# ub-1.net
KiCad netlist of a schematic drawn in EAGLE
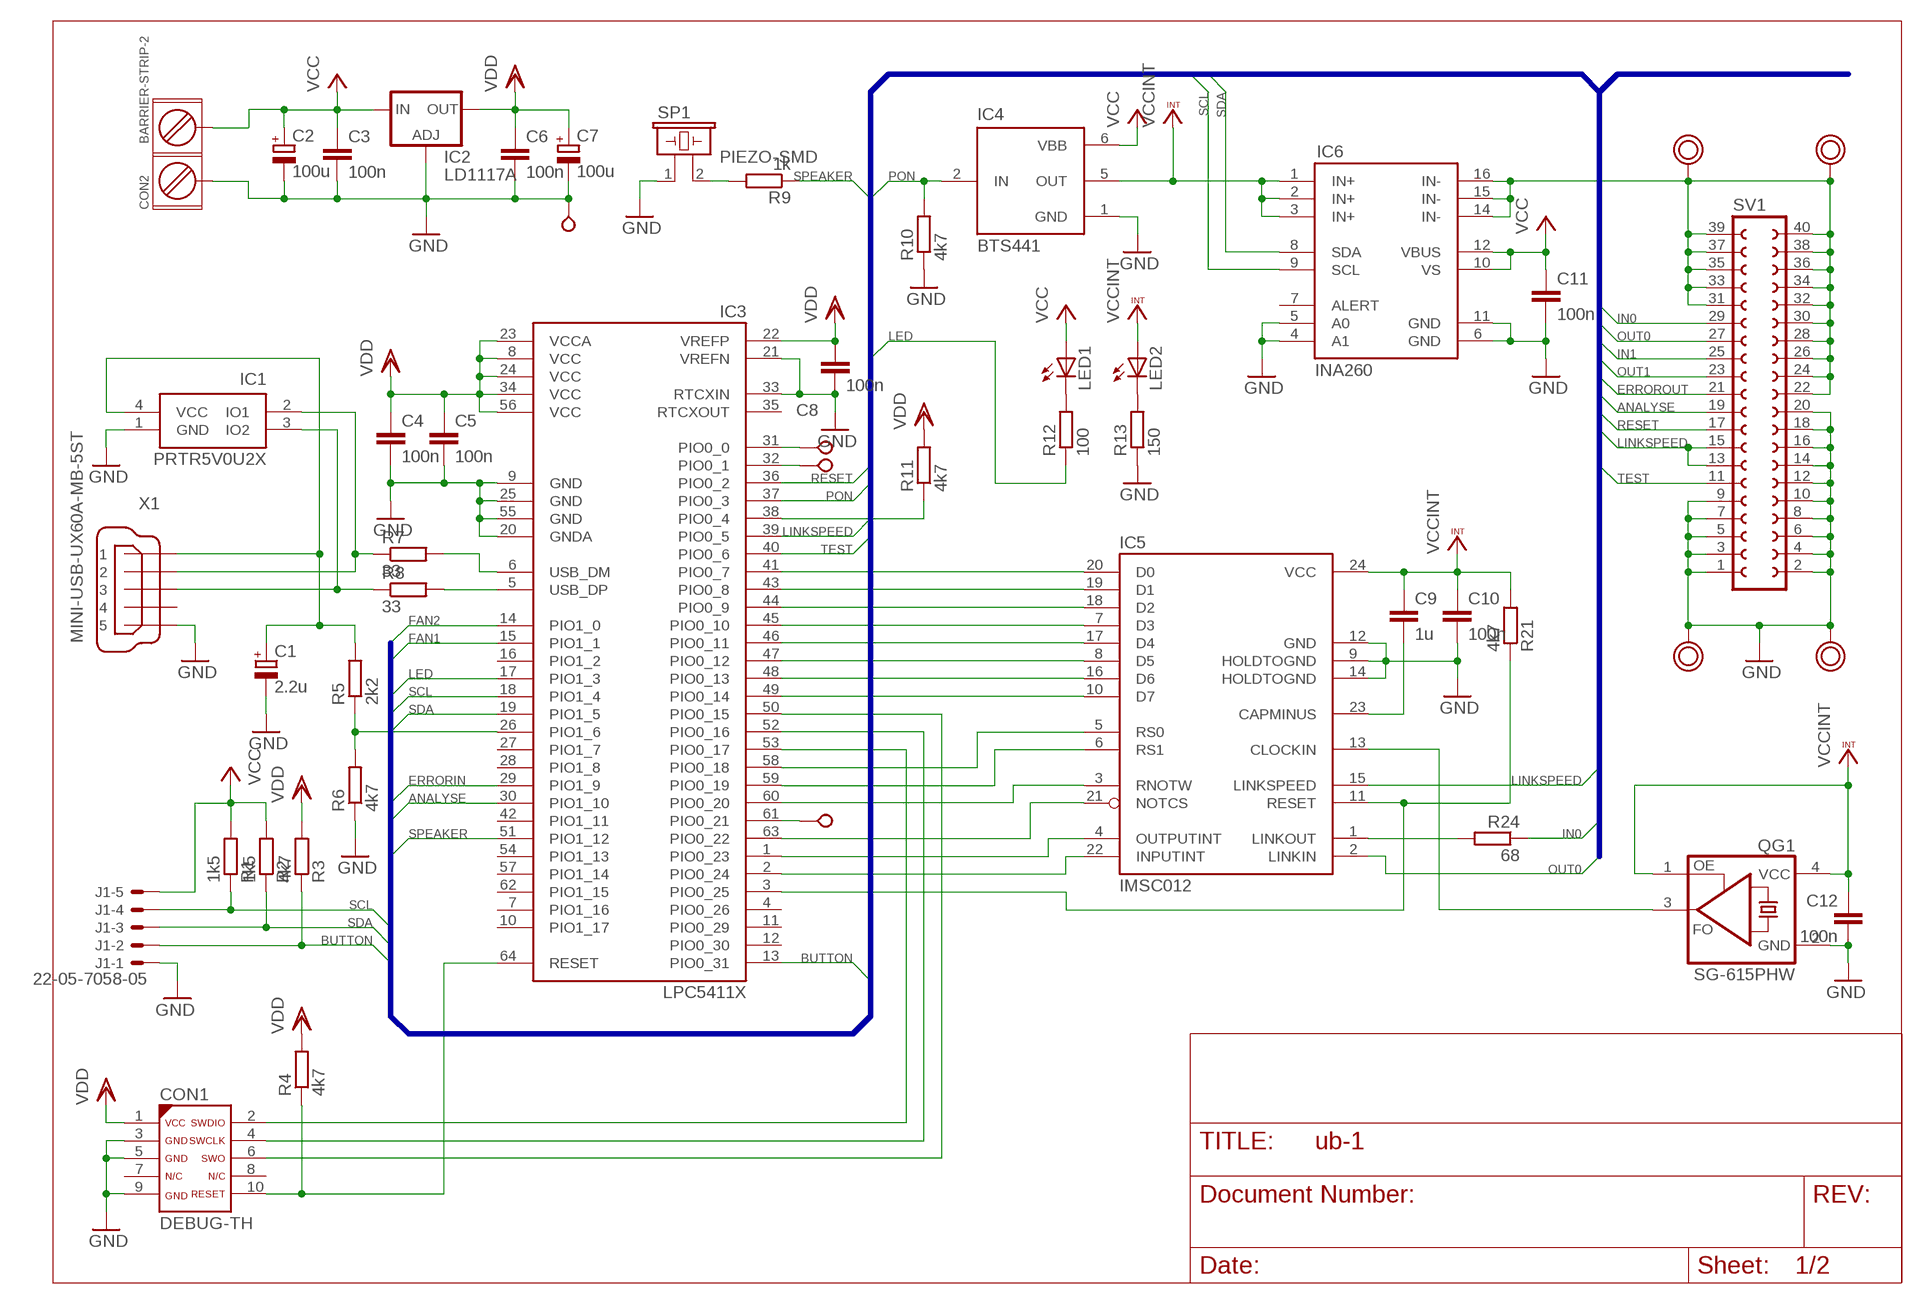
[diagram p0: schematic, sheet 1]
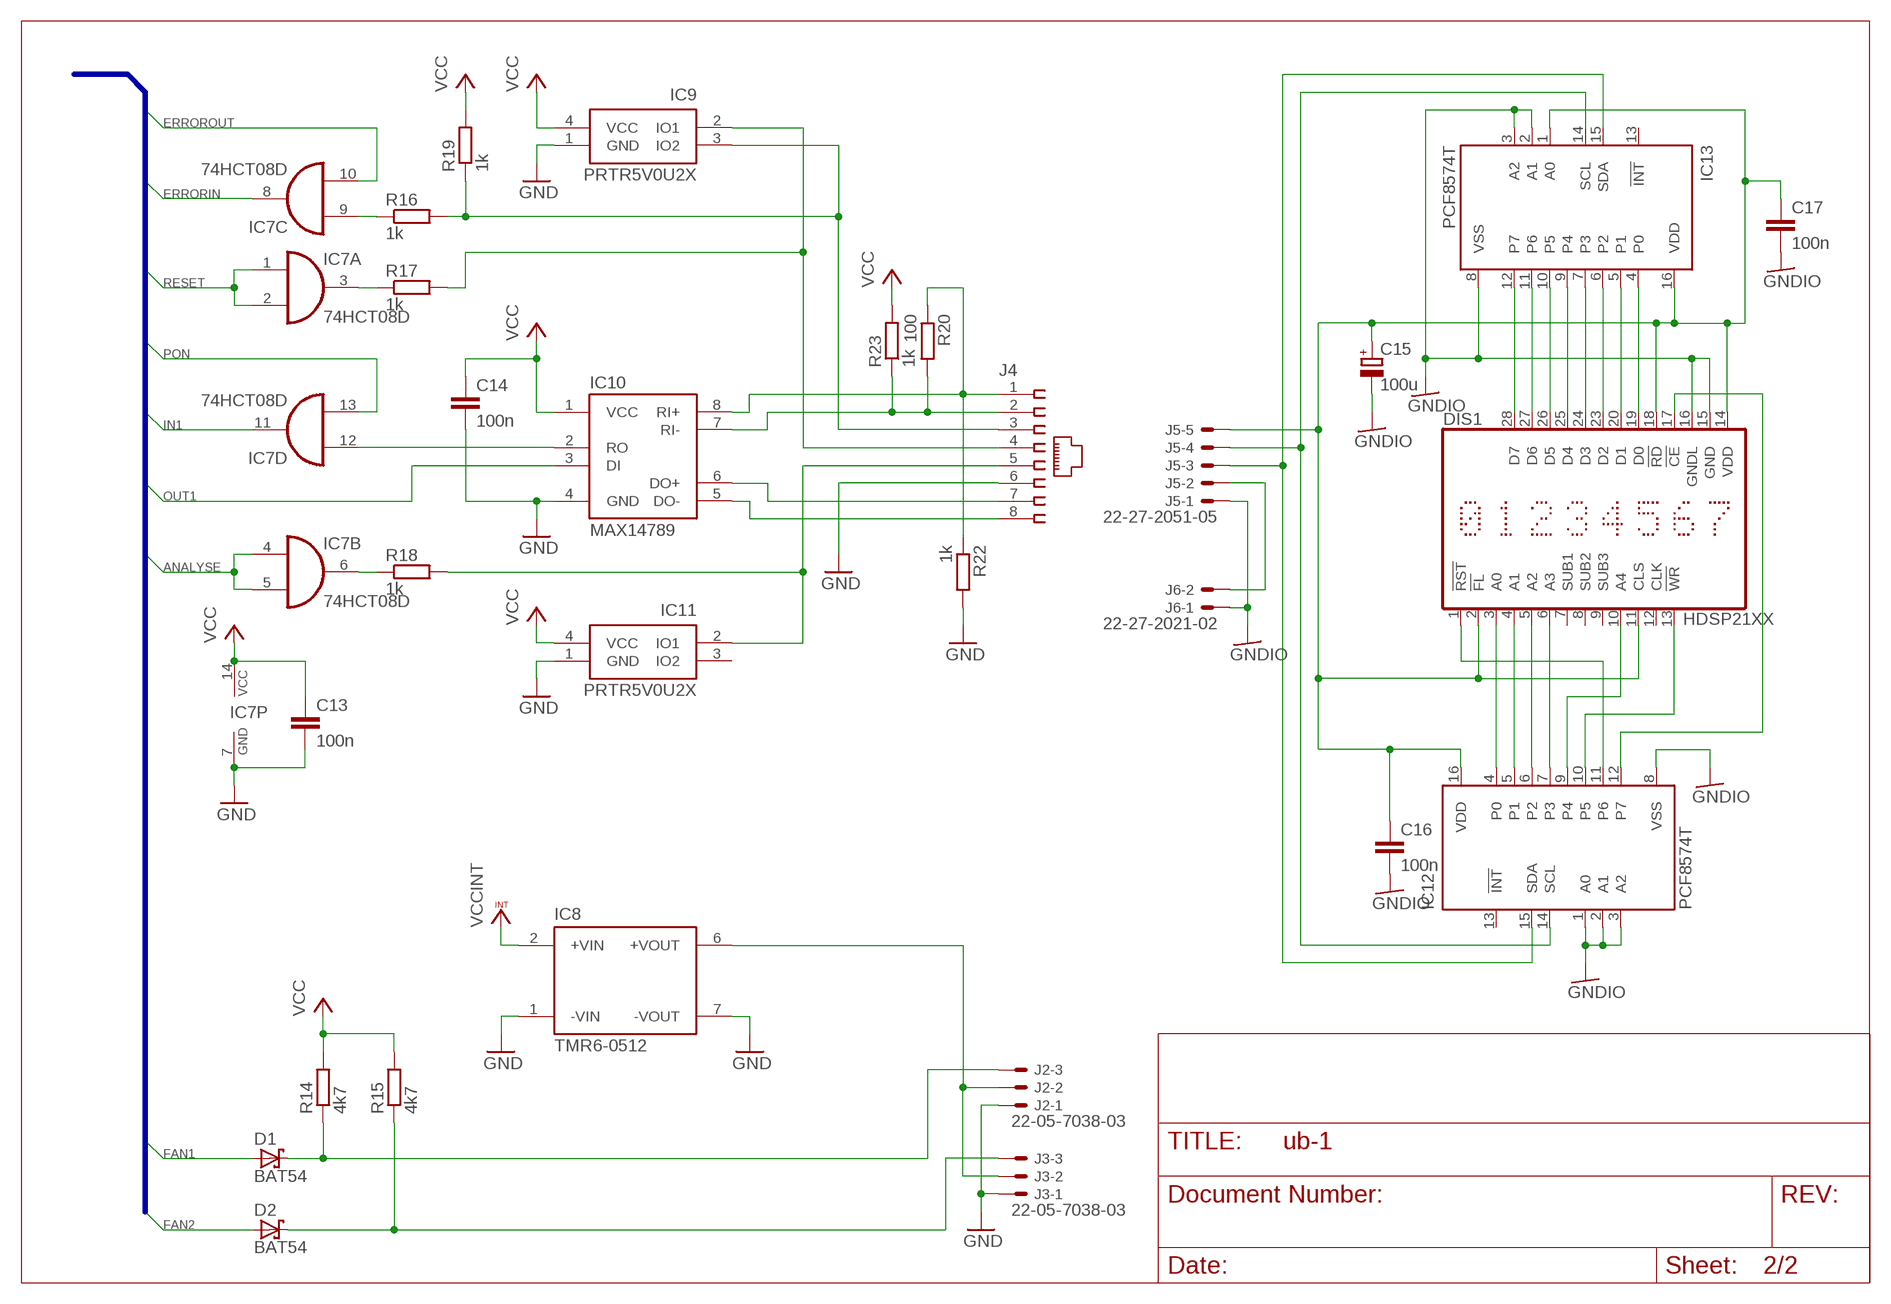
[diagram p1: schematic, sheet 2]

(export (version "E")
  (design (tool "Eeschema 10.0.6"))
  (components
    (comp (ref "C13")
      (value "100n")
      (footprint "eagle-import:C1206")
      (libsource (lib "eagle-import") (part "C-EUC1206"))
    )
    (comp (ref "C14")
      (value "100n")
      (footprint "eagle-import:C1206")
      (libsource (lib "eagle-import") (part "C-EUC1206"))
    )
    (comp (ref "C15")
      (value "100u")
      (footprint "eagle-import:SMC_B")
      (libsource (lib "eagle-import") (part "CPOL-EUSMCB"))
    )
    (comp (ref "C16")
      (value "100n")
      (footprint "eagle-import:C1206")
      (libsource (lib "eagle-import") (part "C-EUC1206"))
    )
    (comp (ref "C17")
      (value "100n")
      (footprint "eagle-import:C1206")
      (libsource (lib "eagle-import") (part "C-EUC1206"))
    )
    (comp (ref "D1")
      (value "BAT54")
      (footprint "eagle-import:SOT23")
      (libsource (lib "eagle-import") (part "BAT54"))
    )
    (comp (ref "D2")
      (value "BAT54")
      (footprint "eagle-import:SOT23")
      (libsource (lib "eagle-import") (part "BAT54"))
    )
    (comp (ref "DIS1")
      (value "HDSP21XX")
      (footprint "eagle-import:HDSP21XX")
      (fields (field (name "MF") "AGILENT TECHNOLOGIES") (field (name "MPN") "HDSP-2179"))
      (libsource (lib "eagle-import") (part "HDSP21XX"))
    )
    (comp (ref "IC7")
      (value "74HCT08D")
      (footprint "eagle-import:SO14")
      (fields (field (name "DIGIKEY") "296-14862-1-ND"))
      (libsource (lib "eagle-import") (part "7408DHCT"))
    )
    (comp (ref "IC8")
      (value "TMR6-0512")
      (footprint "eagle-import:TMR6-0512")
      (libsource (lib "eagle-import") (part "TMR6-0512"))
    )
    (comp (ref "IC9")
      (value "PRTR5V0U2X")
      (footprint "eagle-import:SOT143")
      (libsource (lib "eagle-import") (part "PRTR5V0U2X"))
    )
    (comp (ref "IC10")
      (value "MAX14789")
      (footprint "eagle-import:SO8")
      (libsource (lib "eagle-import") (part "DS8921"))
    )
    (comp (ref "IC11")
      (value "PRTR5V0U2X")
      (footprint "eagle-import:SOT143")
      (libsource (lib "eagle-import") (part "PRTR5V0U2X"))
    )
    (comp (ref "IC12")
      (value "PCF8574T")
      (footprint "eagle-import:SO16W")
      (fields (field (name "MPN") "PCF8574T/3,512"))
      (libsource (lib "eagle-import") (part "PCF8574T"))
    )
    (comp (ref "IC13")
      (value "PCF8574T")
      (footprint "eagle-import:SO16W")
      (fields (field (name "MPN") "PCF8574T/3,512"))
      (libsource (lib "eagle-import") (part "PCF8574T"))
    )
    (comp (ref "J2")
      (value "22-05-7038-03")
      (footprint "eagle-import:7395-03")
      (fields (field (name "DIGIKEY") "WM2785-ND"))
      (libsource (lib "eagle-import") (part "22-?-0305-7038"))
    )
    (comp (ref "J3")
      (value "22-05-7038-03")
      (footprint "eagle-import:7395-03")
      (fields (field (name "DIGIKEY") "WM2785-ND"))
      (libsource (lib "eagle-import") (part "22-?-0305-7038"))
    )
    (comp (ref "J4")
      (value "555164-1")
      (footprint "eagle-import:555164-1")
      (libsource (lib "eagle-import") (part "555164-1"))
    )
    (comp (ref "J5")
      (value "22-27-2051-05")
      (footprint "eagle-import:6410-05")
      (fields (field (name "DIGIKEY") "WM4114-ND"))
      (libsource (lib "eagle-import") (part "22-?-0527-2051"))
    )
    (comp (ref "J6")
      (value "22-27-2021-02")
      (footprint "eagle-import:6410-02")
      (fields (field (name "DIGIKEY") "WM4111-ND"))
      (libsource (lib "eagle-import") (part "22-?-0227-2021"))
    )
    (comp (ref "R14")
      (value "4k7")
      (footprint "eagle-import:R1206")
      (libsource (lib "eagle-import") (part "R-EU_R1206"))
    )
    (comp (ref "R15")
      (value "4k7")
      (footprint "eagle-import:R1206")
      (libsource (lib "eagle-import") (part "R-EU_R1206"))
    )
    (comp (ref "R16")
      (value "1k")
      (footprint "eagle-import:R1206")
      (libsource (lib "eagle-import") (part "R-EU_R1206"))
    )
    (comp (ref "R17")
      (value "1k")
      (footprint "eagle-import:R1206")
      (libsource (lib "eagle-import") (part "R-EU_R1206"))
    )
    (comp (ref "R18")
      (value "1k")
      (footprint "eagle-import:R1206")
      (libsource (lib "eagle-import") (part "R-EU_R1206"))
    )
    (comp (ref "R19")
      (value "1k")
      (footprint "eagle-import:R1206")
      (libsource (lib "eagle-import") (part "R-EU_R1206"))
    )
    (comp (ref "R20")
      (value "100")
      (footprint "eagle-import:R1206")
      (libsource (lib "eagle-import") (part "R-EU_R1206"))
    )
    (comp (ref "R22")
      (value "1k")
      (footprint "eagle-import:R1206")
      (libsource (lib "eagle-import") (part "R-EU_R1206"))
    )
    (comp (ref "R23")
      (value "1k")
      (footprint "eagle-import:R1206")
      (libsource (lib "eagle-import") (part "R-EU_R1206"))
    )
    (comp (ref "C1")
      (value "2.2u")
      (footprint "eagle-import:SMC_B")
      (libsource (lib "eagle-import") (part "CPOL-EUSMCB"))
    )
    (comp (ref "C2")
      (value "100u")
      (footprint "eagle-import:SMC_B")
      (libsource (lib "eagle-import") (part "CPOL-EUSMCB"))
    )
    (comp (ref "C3")
      (value "100n")
      (footprint "eagle-import:C1206")
      (libsource (lib "eagle-import") (part "C-EUC1206"))
    )
    (comp (ref "C4")
      (value "100n")
      (footprint "eagle-import:C1206")
      (libsource (lib "eagle-import") (part "C-EUC1206"))
    )
    (comp (ref "C5")
      (value "100n")
      (footprint "eagle-import:C1206")
      (libsource (lib "eagle-import") (part "C-EUC1206"))
    )
    (comp (ref "C6")
      (value "100n")
      (footprint "eagle-import:C1206")
      (libsource (lib "eagle-import") (part "C-EUC1206"))
    )
    (comp (ref "C7")
      (value "100u")
      (footprint "eagle-import:SMC_B")
      (libsource (lib "eagle-import") (part "CPOL-EUSMCB"))
    )
    (comp (ref "C8")
      (value "100n")
      (footprint "eagle-import:C1206")
      (libsource (lib "eagle-import") (part "C-EUC1206"))
    )
    (comp (ref "C9")
      (value "1u")
      (footprint "eagle-import:C1206")
      (libsource (lib "eagle-import") (part "C-EUC1206"))
    )
    (comp (ref "C10")
      (value "100n")
      (footprint "eagle-import:C1206")
      (libsource (lib "eagle-import") (part "C-EUC1206"))
    )
    (comp (ref "C11")
      (value "100n")
      (footprint "eagle-import:C1206")
      (libsource (lib "eagle-import") (part "C-EUC1206"))
    )
    (comp (ref "C12")
      (value "100n")
      (footprint "eagle-import:C1206")
      (libsource (lib "eagle-import") (part "C-EUC1206"))
    )
    (comp (ref "CON1")
      (value "DEBUG-TH")
      (footprint "eagle-import:DEBUG-TH")
      (libsource (lib "eagle-import") (part "DEBUG-TH"))
    )
    (comp (ref "CON2")
      (value "BARRIER-STRIP-2")
      (footprint "eagle-import:BARRIER-STRIP-2")
      (libsource (lib "eagle-import") (part "BARRIER-STRIP-2"))
    )
    (comp (ref "IC1")
      (value "PRTR5V0U2X")
      (footprint "eagle-import:SOT143")
      (libsource (lib "eagle-import") (part "PRTR5V0U2X"))
    )
    (comp (ref "IC2")
      (value "LD1117A")
      (footprint "eagle-import:SOT223")
      (libsource (lib "eagle-import") (part "LD1117A"))
    )
    (comp (ref "IC3")
      (value "LPC5411X")
      (footprint "eagle-import:LQPF64")
      (libsource (lib "eagle-import") (part "LPC5411X"))
    )
    (comp (ref "IC4")
      (value "BTS441")
      (footprint "eagle-import:TO263-4")
      (libsource (lib "eagle-import") (part "BTS441"))
    )
    (comp (ref "IC5")
      (value "IMSC012")
      (footprint "eagle-import:DIL24-3")
      (libsource (lib "eagle-import") (part "IMSC012"))
    )
    (comp (ref "IC6")
      (value "INA260")
      (footprint "eagle-import:TSSOP-16")
      (libsource (lib "eagle-import") (part "INA260"))
    )
    (comp (ref "J1")
      (value "22-05-7058-05")
      (footprint "eagle-import:7395-05")
      (fields (field (name "DIGIKEY") "WM2787-ND"))
      (libsource (lib "eagle-import") (part "22-?-0505-7058"))
    )
    (comp (ref "LED1")
      (value "LEDSMT1206")
      (footprint "eagle-import:1206")
      (libsource (lib "eagle-import") (part "LEDSMT1206"))
    )
    (comp (ref "LED2")
      (value "LEDSMT1206")
      (footprint "eagle-import:1206")
      (libsource (lib "eagle-import") (part "LEDSMT1206"))
    )
    (comp (ref "QG1")
      (value "SG-615PHW")
      (footprint "eagle-import:SG-615")
      (libsource (lib "eagle-import") (part "SG-615PHW"))
    )
    (comp (ref "R1")
      (value "1k5")
      (footprint "eagle-import:R1206")
      (libsource (lib "eagle-import") (part "R-EU_R1206"))
    )
    (comp (ref "R2")
      (value "1k5")
      (footprint "eagle-import:R1206")
      (libsource (lib "eagle-import") (part "R-EU_R1206"))
    )
    (comp (ref "R3")
      (value "4k7")
      (footprint "eagle-import:R1206")
      (libsource (lib "eagle-import") (part "R-EU_R1206"))
    )
    (comp (ref "R4")
      (value "4k7")
      (footprint "eagle-import:R1206")
      (libsource (lib "eagle-import") (part "R-EU_R1206"))
    )
    (comp (ref "R5")
      (value "2k2")
      (footprint "eagle-import:R1206")
      (libsource (lib "eagle-import") (part "R-EU_R1206"))
    )
    (comp (ref "R6")
      (value "4k7")
      (footprint "eagle-import:R1206")
      (libsource (lib "eagle-import") (part "R-EU_R1206"))
    )
    (comp (ref "R7")
      (value "33")
      (footprint "eagle-import:R1206")
      (libsource (lib "eagle-import") (part "R-EU_R1206"))
    )
    (comp (ref "R8")
      (value "33")
      (footprint "eagle-import:R1206")
      (libsource (lib "eagle-import") (part "R-EU_R1206"))
    )
    (comp (ref "R9")
      (value "1k")
      (footprint "eagle-import:R1206")
      (libsource (lib "eagle-import") (part "R-EU_R1206"))
    )
    (comp (ref "R10")
      (value "4k7")
      (footprint "eagle-import:R1206")
      (libsource (lib "eagle-import") (part "R-EU_R1206"))
    )
    (comp (ref "R11")
      (value "4k7")
      (footprint "eagle-import:R1206")
      (libsource (lib "eagle-import") (part "R-EU_R1206"))
    )
    (comp (ref "R12")
      (value "100")
      (footprint "eagle-import:R1206")
      (libsource (lib "eagle-import") (part "R-EU_R1206"))
    )
    (comp (ref "R13")
      (value "150")
      (footprint "eagle-import:R1206")
      (libsource (lib "eagle-import") (part "R-EU_R1206"))
    )
    (comp (ref "R21")
      (value "4k7")
      (footprint "eagle-import:R1206")
      (libsource (lib "eagle-import") (part "R-EU_R1206"))
    )
    (comp (ref "R24")
      (value "68")
      (footprint "eagle-import:R1206")
      (libsource (lib "eagle-import") (part "R-EU_R1206"))
    )
    (comp (ref "SCREW1")
      (value "POWERPAD")
      (footprint "eagle-import:POWERPAD")
      (libsource (lib "eagle-import") (part "POWERPAD"))
    )
    (comp (ref "SCREW2")
      (value "POWERPAD")
      (footprint "eagle-import:POWERPAD")
      (libsource (lib "eagle-import") (part "POWERPAD"))
    )
    (comp (ref "SCREW3")
      (value "POWERPAD")
      (footprint "eagle-import:POWERPAD")
      (libsource (lib "eagle-import") (part "POWERPAD"))
    )
    (comp (ref "SCREW4")
      (value "POWERPAD")
      (footprint "eagle-import:POWERPAD")
      (libsource (lib "eagle-import") (part "POWERPAD"))
    )
    (comp (ref "SP1")
      (value "PIEZO-SMD")
      (footprint "eagle-import:PIEZO-SMD")
      (libsource (lib "eagle-import") (part "PIEZO-SMD"))
    )
    (comp (ref "SV1")
      (value "FE20-2")
      (footprint "eagle-import:FE20-2")
      (libsource (lib "eagle-import") (part "FE20-2"))
    )
    (comp (ref "TP1")
      (value "TESTPOINT")
      (footprint "eagle-import:VERO_TP")
      (libsource (lib "eagle-import") (part "TESTPOINT"))
    )
    (comp (ref "TP2")
      (value "TESTPOINT")
      (footprint "eagle-import:VERO_TP")
      (libsource (lib "eagle-import") (part "TESTPOINT"))
    )
    (comp (ref "TP3")
      (value "TESTPOINT")
      (footprint "eagle-import:VERO_TP")
      (libsource (lib "eagle-import") (part "TESTPOINT"))
    )
    (comp (ref "TP4")
      (value "TESTPOINT")
      (footprint "eagle-import:VERO_TP")
      (libsource (lib "eagle-import") (part "TESTPOINT"))
    )
    (comp (ref "X1")
      (value "MINI-USB-UX60A-MB-5ST")
      (footprint "eagle-import:UX60A-MB-5ST")
      (libsource (lib "eagle-import") (part "MINI-USB-UX60A-MB-5ST"))
    )
  )
  (nets
    (net (code "1") (name "ANALYSE") (class "Default")
      (node (ref "IC3") (pin "30") (pinfunction "PIO1_10_30") (pintype "tri_state"))
      (node (ref "IC7") (pin "4") (pinfunction "I0_4") (pintype "input"))
      (node (ref "IC7") (pin "5") (pinfunction "I1_5") (pintype "input"))
      (node (ref "SV1") (pin "19") (pinfunction "19_19") (pintype "passive"))
    )
    (net (code "2") (name "BUTTON") (class "Default")
      (node (ref "IC3") (pin "13") (pinfunction "PIO0_31_13") (pintype "tri_state"))
      (node (ref "J1") (pin "2") (pinfunction "S_2") (pintype "passive"))
      (node (ref "R3") (pin "1") (pinfunction "1_1") (pintype "passive"))
    )
    (net (code "3") (name "ERRORIN") (class "Default")
      (node (ref "IC3") (pin "29") (pinfunction "PIO1_9_29") (pintype "tri_state"))
      (node (ref "IC7") (pin "8") (pinfunction "O_8") (pintype "output"))
    )
    (net (code "4") (name "ERROROUT") (class "Default")
      (node (ref "IC7") (pin "10") (pinfunction "I1_10") (pintype "input"))
      (node (ref "SV1") (pin "21") (pinfunction "21_21") (pintype "passive"))
    )
    (net (code "5") (name "FAN1") (class "Default")
      (node (ref "D1") (pin "1") (pinfunction "A_1") (pintype "passive"))
      (node (ref "IC3") (pin "15") (pinfunction "PIO1_1_15") (pintype "tri_state"))
    )
    (net (code "6") (name "FAN2") (class "Default")
      (node (ref "D2") (pin "1") (pinfunction "A_1") (pintype "passive"))
      (node (ref "IC3") (pin "14") (pinfunction "PIO1_0_14") (pintype "tri_state"))
    )
    (net (code "7") (name "GND") (class "Default")
      (node (ref "C1") (pin "-") (pinfunction "-_-") (pintype "passive"))
      (node (ref "C10") (pin "2") (pinfunction "2_2") (pintype "passive"))
      (node (ref "C11") (pin "2") (pinfunction "2_2") (pintype "passive"))
      (node (ref "C12") (pin "2") (pinfunction "2_2") (pintype "passive"))
      (node (ref "C13") (pin "2") (pinfunction "2_2") (pintype "passive"))
      (node (ref "C14") (pin "2") (pinfunction "2_2") (pintype "passive"))
      (node (ref "C2") (pin "-") (pinfunction "-_-") (pintype "passive"))
      (node (ref "C3") (pin "2") (pinfunction "2_2") (pintype "passive"))
      (node (ref "C4") (pin "2") (pinfunction "2_2") (pintype "passive"))
      (node (ref "C5") (pin "2") (pinfunction "2_2") (pintype "passive"))
      (node (ref "C6") (pin "2") (pinfunction "2_2") (pintype "passive"))
      (node (ref "C7") (pin "-") (pinfunction "-_-") (pintype "passive"))
      (node (ref "C8") (pin "2") (pinfunction "2_2") (pintype "passive"))
      (node (ref "CON1") (pin "3") (pinfunction "3_3") (pintype "passive"))
      (node (ref "CON1") (pin "5") (pinfunction "5_5") (pintype "passive"))
      (node (ref "CON1") (pin "9") (pinfunction "9_9") (pintype "passive"))
      (node (ref "CON2") (pin "1") (pinfunction "1_1") (pintype "passive"))
      (node (ref "IC1") (pin "1") (pinfunction "GND_1") (pintype "power_in"))
      (node (ref "IC10") (pin "4") (pinfunction "GND_4") (pintype "power_in"))
      (node (ref "IC11") (pin "1") (pinfunction "GND_1") (pintype "power_in"))
      (node (ref "IC2") (pin "1") (pinfunction "ADJ_1") (pintype "input"))
      (node (ref "IC3") (pin "20") (pinfunction "GNDA_20") (pintype "power_in"))
      (node (ref "IC3") (pin "21") (pinfunction "VREFN_21") (pintype "tri_state"))
      (node (ref "IC3") (pin "25") (pinfunction "GND_25") (pintype "power_in"))
      (node (ref "IC3") (pin "33") (pinfunction "RTCXIN_33") (pintype "tri_state"))
      (node (ref "IC3") (pin "55") (pinfunction "GND_55") (pintype "power_in"))
      (node (ref "IC3") (pin "9") (pinfunction "GND_9") (pintype "power_in"))
      (node (ref "IC4") (pin "1") (pinfunction "GND_1") (pintype "power_in"))
      (node (ref "IC5") (pin "12") (pinfunction "GND_12") (pintype "power_in"))
      (node (ref "IC5") (pin "14") (pinfunction "HOLDTOGND_14") (pintype "input"))
      (node (ref "IC5") (pin "9") (pinfunction "HOLDTOGND_9") (pintype "input"))
      (node (ref "IC6") (pin "11") (pinfunction "GND_11") (pintype "power_in"))
      (node (ref "IC6") (pin "4") (pinfunction "A1_4") (pintype "input"))
      (node (ref "IC6") (pin "5") (pinfunction "A0_5") (pintype "input"))
      (node (ref "IC6") (pin "6") (pinfunction "GND_6") (pintype "power_in"))
      (node (ref "IC7") (pin "7") (pinfunction "GND_7") (pintype "power_in"))
      (node (ref "IC8") (pin "1") (pinfunction "-VIN_1") (pintype "passive"))
      (node (ref "IC8") (pin "7") (pinfunction "-VOUT_7") (pintype "passive"))
      (node (ref "IC9") (pin "1") (pinfunction "GND_1") (pintype "power_in"))
      (node (ref "J1") (pin "1") (pinfunction "S_1") (pintype "passive"))
      (node (ref "J2") (pin "1") (pinfunction "S_1") (pintype "passive"))
      (node (ref "J3") (pin "1") (pinfunction "S_1") (pintype "passive"))
      (node (ref "J4") (pin "6") (pinfunction "6_6") (pintype "passive"))
      (node (ref "QG1") (pin "2") (pinfunction "GND_2") (pintype "power_in"))
      (node (ref "R10") (pin "1") (pinfunction "1_1") (pintype "passive"))
      (node (ref "R13") (pin "1") (pinfunction "1_1") (pintype "passive"))
      (node (ref "R22") (pin "2") (pinfunction "2_2") (pintype "passive"))
      (node (ref "R6") (pin "1") (pinfunction "1_1") (pintype "passive"))
      (node (ref "SCREW2") (pin "P$1") (pinfunction "P$1_P$1") (pintype "bidirectional"))
      (node (ref "SCREW4") (pin "P$1") (pinfunction "P$1_P$1") (pintype "bidirectional"))
      (node (ref "SP1") (pin "1") (pinfunction "1_1") (pintype "passive"))
      (node (ref "SV1") (pin "1") (pinfunction "1_1") (pintype "passive"))
      (node (ref "SV1") (pin "10") (pinfunction "10_10") (pintype "passive"))
      (node (ref "SV1") (pin "12") (pinfunction "12_12") (pintype "passive"))
      (node (ref "SV1") (pin "14") (pinfunction "14_14") (pintype "passive"))
      (node (ref "SV1") (pin "16") (pinfunction "16_16") (pintype "passive"))
      (node (ref "SV1") (pin "18") (pinfunction "18_18") (pintype "passive"))
      (node (ref "SV1") (pin "2") (pinfunction "2_2") (pintype "passive"))
      (node (ref "SV1") (pin "20") (pinfunction "20_20") (pintype "passive"))
      (node (ref "SV1") (pin "3") (pinfunction "3_3") (pintype "passive"))
      (node (ref "SV1") (pin "4") (pinfunction "4_4") (pintype "passive"))
      (node (ref "SV1") (pin "5") (pinfunction "5_5") (pintype "passive"))
      (node (ref "SV1") (pin "6") (pinfunction "6_6") (pintype "passive"))
      (node (ref "SV1") (pin "7") (pinfunction "7_7") (pintype "passive"))
      (node (ref "SV1") (pin "8") (pinfunction "8_8") (pintype "passive"))
      (node (ref "SV1") (pin "9") (pinfunction "9_9") (pintype "passive"))
      (node (ref "TP3") (pin "P$1") (pinfunction "P$1_P$1") (pintype "passive"))
      (node (ref "X1") (pin "5") (pinfunction "5_5") (pintype "input"))
    )
    (net (code "8") (name "GNDIO") (class "Default")
      (node (ref "C15") (pin "-") (pinfunction "-_-") (pintype "passive"))
      (node (ref "C16") (pin "2") (pinfunction "2_2") (pintype "passive"))
      (node (ref "C17") (pin "2") (pinfunction "2_2") (pintype "passive"))
      (node (ref "DIS1") (pin "15") (pinfunction "GND_15") (pintype "power_in"))
      (node (ref "DIS1") (pin "16") (pinfunction "GNDL_16") (pintype "power_in"))
      (node (ref "IC12") (pin "1") (pinfunction "A0_1") (pintype "input"))
      (node (ref "IC12") (pin "2") (pinfunction "A1_2") (pintype "input"))
      (node (ref "IC12") (pin "3") (pinfunction "A2_3") (pintype "input"))
      (node (ref "IC12") (pin "8") (pinfunction "VSS_8") (pintype "power_in"))
      (node (ref "IC13") (pin "2") (pinfunction "A1_2") (pintype "input"))
      (node (ref "IC13") (pin "3") (pinfunction "A2_3") (pintype "input"))
      (node (ref "IC13") (pin "8") (pinfunction "VSS_8") (pintype "power_in"))
      (node (ref "J5") (pin "1") (pinfunction "S_1") (pintype "passive"))
      (node (ref "J6") (pin "1") (pinfunction "S_1") (pintype "passive"))
    )
    (net (code "9") (name "IN0") (class "Default")
      (node (ref "R24") (pin "1") (pinfunction "1_1") (pintype "passive"))
      (node (ref "SV1") (pin "29") (pinfunction "29_29") (pintype "passive"))
    )
    (net (code "10") (name "IN1") (class "Default")
      (node (ref "IC7") (pin "11") (pinfunction "O_11") (pintype "output"))
      (node (ref "SV1") (pin "25") (pinfunction "25_25") (pintype "passive"))
    )
    (net (code "11") (name "LED") (class "Default")
      (node (ref "IC3") (pin "17") (pinfunction "PIO1_3_17") (pintype "tri_state"))
      (node (ref "R12") (pin "1") (pinfunction "1_1") (pintype "passive"))
    )
    (net (code "12") (name "LINKSPEED") (class "Default")
      (node (ref "IC3") (pin "39") (pinfunction "PIO0_5_39") (pintype "tri_state"))
      (node (ref "IC5") (pin "15") (pinfunction "LINKSPEED_15") (pintype "input"))
      (node (ref "SV1") (pin "13") (pinfunction "13_13") (pintype "passive"))
      (node (ref "SV1") (pin "15") (pinfunction "15_15") (pintype "passive"))
    )
    (net (code "13") (name "Net-(D1-C)") (class "Default")
      (node (ref "D1") (pin "3") (pinfunction "C_3") (pintype "passive"))
      (node (ref "J2") (pin "3") (pinfunction "S_3") (pintype "passive"))
      (node (ref "R14") (pin "1") (pinfunction "1_1") (pintype "passive"))
    )
    (net (code "14") (name "Net-(D2-C)") (class "Default")
      (node (ref "D2") (pin "3") (pinfunction "C_3") (pintype "passive"))
      (node (ref "J3") (pin "3") (pinfunction "S_3") (pintype "passive"))
      (node (ref "R15") (pin "1") (pinfunction "1_1") (pintype "passive"))
    )
    (net (code "15") (name "Net-(DIS1-A0)") (class "Default")
      (node (ref "DIS1") (pin "3") (pinfunction "A0_3") (pintype "input"))
      (node (ref "IC12") (pin "4") (pinfunction "P0_4") (pintype "bidirectional"))
    )
    (net (code "16") (name "Net-(DIS1-A1)") (class "Default")
      (node (ref "DIS1") (pin "4") (pinfunction "A1_4") (pintype "input"))
      (node (ref "IC12") (pin "5") (pinfunction "P1_5") (pintype "bidirectional"))
    )
    (net (code "17") (name "Net-(DIS1-A2)") (class "Default")
      (node (ref "DIS1") (pin "5") (pinfunction "A2_5") (pintype "input"))
      (node (ref "IC12") (pin "6") (pinfunction "P2_6") (pintype "bidirectional"))
    )
    (net (code "18") (name "Net-(DIS1-A3)") (class "Default")
      (node (ref "DIS1") (pin "6") (pinfunction "A3_6") (pintype "input"))
      (node (ref "IC12") (pin "7") (pinfunction "P3_7") (pintype "bidirectional"))
    )
    (net (code "19") (name "Net-(DIS1-A4)") (class "Default")
      (node (ref "DIS1") (pin "10") (pinfunction "A4_10") (pintype "input"))
      (node (ref "IC12") (pin "9") (pinfunction "P4_9") (pintype "bidirectional"))
    )
    (net (code "20") (name "Net-(DIS1-CLS)") (class "Default")
      (node (ref "C15") (pin "+") (pinfunction "+_+") (pintype "passive"))
      (node (ref "C16") (pin "1") (pinfunction "1_1") (pintype "passive"))
      (node (ref "C17") (pin "1") (pinfunction "1_1") (pintype "passive"))
      (node (ref "DIS1") (pin "11") (pinfunction "CLS_11") (pintype "input"))
      (node (ref "DIS1") (pin "14") (pinfunction "VDD_14") (pintype "power_in"))
      (node (ref "DIS1") (pin "18") (pinfunction "~{RD}_18") (pintype "input"))
      (node (ref "DIS1") (pin "2") (pinfunction "~{FL}_2") (pintype "input"))
      (node (ref "IC12") (pin "16") (pinfunction "VDD_16") (pintype "power_in"))
      (node (ref "IC13") (pin "1") (pinfunction "A0_1") (pintype "input"))
      (node (ref "IC13") (pin "16") (pinfunction "VDD_16") (pintype "power_in"))
      (node (ref "J5") (pin "5") (pinfunction "S_5") (pintype "passive"))
    )
    (net (code "21") (name "Net-(DIS1-D0)") (class "Default")
      (node (ref "DIS1") (pin "19") (pinfunction "D0_19") (pintype "input"))
      (node (ref "IC13") (pin "4") (pinfunction "P0_4") (pintype "bidirectional"))
    )
    (net (code "22") (name "Net-(DIS1-D1)") (class "Default")
      (node (ref "DIS1") (pin "20") (pinfunction "D1_20") (pintype "input"))
      (node (ref "IC13") (pin "5") (pinfunction "P1_5") (pintype "bidirectional"))
    )
    (net (code "23") (name "Net-(DIS1-D2)") (class "Default")
      (node (ref "DIS1") (pin "23") (pinfunction "D2_23") (pintype "input"))
      (node (ref "IC13") (pin "6") (pinfunction "P2_6") (pintype "bidirectional"))
    )
    (net (code "24") (name "Net-(DIS1-D3)") (class "Default")
      (node (ref "DIS1") (pin "24") (pinfunction "D3_24") (pintype "input"))
      (node (ref "IC13") (pin "7") (pinfunction "P3_7") (pintype "bidirectional"))
    )
    (net (code "25") (name "Net-(DIS1-D4)") (class "Default")
      (node (ref "DIS1") (pin "25") (pinfunction "D4_25") (pintype "input"))
      (node (ref "IC13") (pin "9") (pinfunction "P4_9") (pintype "bidirectional"))
    )
    (net (code "26") (name "Net-(DIS1-D5)") (class "Default")
      (node (ref "DIS1") (pin "26") (pinfunction "D5_26") (pintype "input"))
      (node (ref "IC13") (pin "10") (pinfunction "P5_10") (pintype "bidirectional"))
    )
    (net (code "27") (name "Net-(DIS1-D6)") (class "Default")
      (node (ref "DIS1") (pin "27") (pinfunction "D6_27") (pintype "input"))
      (node (ref "IC13") (pin "11") (pinfunction "P6_11") (pintype "bidirectional"))
    )
    (net (code "28") (name "Net-(DIS1-D7)") (class "Default")
      (node (ref "DIS1") (pin "28") (pinfunction "D7_28") (pintype "input"))
      (node (ref "IC13") (pin "12") (pinfunction "P7_12") (pintype "bidirectional"))
    )
    (net (code "29") (name "Net-(DIS1-~{CE})") (class "Default")
      (node (ref "DIS1") (pin "17") (pinfunction "~{CE}_17") (pintype "input"))
      (node (ref "IC12") (pin "12") (pinfunction "P7_12") (pintype "bidirectional"))
    )
    (net (code "30") (name "Net-(DIS1-~{RST})") (class "Default")
      (node (ref "DIS1") (pin "1") (pinfunction "~{RST}_1") (pintype "input"))
      (node (ref "IC12") (pin "11") (pinfunction "P6_11") (pintype "bidirectional"))
    )
    (net (code "31") (name "Net-(DIS1-~{WR})") (class "Default")
      (node (ref "DIS1") (pin "13") (pinfunction "~{WR}_13") (pintype "input"))
      (node (ref "IC12") (pin "10") (pinfunction "P5_10") (pintype "bidirectional"))
    )
    (net (code "32") (name "Net-(IC1-IO1)") (class "Default")
      (node (ref "IC1") (pin "2") (pinfunction "IO1_2") (pintype "passive"))
      (node (ref "R7") (pin "1") (pinfunction "1_1") (pintype "passive"))
      (node (ref "X1") (pin "2") (pinfunction "2_2") (pintype "input"))
    )
    (net (code "33") (name "Net-(IC1-IO2)") (class "Default")
      (node (ref "IC1") (pin "3") (pinfunction "IO2_3") (pintype "passive"))
      (node (ref "R8") (pin "1") (pinfunction "1_1") (pintype "passive"))
      (node (ref "X1") (pin "3") (pinfunction "3_3") (pintype "input"))
    )
    (net (code "34") (name "Net-(IC1-VCC)") (class "Default")
      (node (ref "C1") (pin "+") (pinfunction "+_+") (pintype "passive"))
      (node (ref "IC1") (pin "4") (pinfunction "VCC_4") (pintype "power_in"))
      (node (ref "R5") (pin "2") (pinfunction "2_2") (pintype "passive"))
      (node (ref "X1") (pin "1") (pinfunction "1_1") (pintype "input"))
    )
    (net (code "35") (name "Net-(IC3-PIO0_0)") (class "Default")
      (node (ref "IC3") (pin "31") (pinfunction "PIO0_0_31") (pintype "tri_state"))
      (node (ref "TP1") (pin "P$1") (pinfunction "P$1_P$1") (pintype "passive"))
    )
    (net (code "36") (name "Net-(IC3-PIO0_1)") (class "Default")
      (node (ref "IC3") (pin "32") (pinfunction "PIO0_1_32") (pintype "tri_state"))
      (node (ref "TP2") (pin "P$1") (pinfunction "P$1_P$1") (pintype "passive"))
    )
    (net (code "37") (name "Net-(IC3-PIO0_4)") (class "Default")
      (node (ref "IC3") (pin "38") (pinfunction "PIO0_4_38") (pintype "tri_state"))
      (node (ref "R11") (pin "1") (pinfunction "1_1") (pintype "passive"))
    )
    (net (code "38") (name "Net-(IC3-PIO0_7)") (class "Default")
      (node (ref "IC3") (pin "41") (pinfunction "PIO0_7_41") (pintype "tri_state"))
      (node (ref "IC5") (pin "20") (pinfunction "D0_20") (pintype "bidirectional"))
    )
    (net (code "39") (name "Net-(IC3-PIO0_8)") (class "Default")
      (node (ref "IC3") (pin "43") (pinfunction "PIO0_8_43") (pintype "tri_state"))
      (node (ref "IC5") (pin "19") (pinfunction "D1_19") (pintype "bidirectional"))
    )
    (net (code "40") (name "Net-(IC3-PIO0_9)") (class "Default")
      (node (ref "IC3") (pin "44") (pinfunction "PIO0_9_44") (pintype "tri_state"))
      (node (ref "IC5") (pin "18") (pinfunction "D2_18") (pintype "bidirectional"))
    )
    (net (code "41") (name "Net-(IC3-PIO0_10)") (class "Default")
      (node (ref "IC3") (pin "45") (pinfunction "PIO0_10_45") (pintype "tri_state"))
      (node (ref "IC5") (pin "7") (pinfunction "D3_7") (pintype "bidirectional"))
    )
    (net (code "42") (name "Net-(IC3-PIO0_11)") (class "Default")
      (node (ref "IC3") (pin "46") (pinfunction "PIO0_11_46") (pintype "tri_state"))
      (node (ref "IC5") (pin "17") (pinfunction "D4_17") (pintype "bidirectional"))
    )
    (net (code "43") (name "Net-(IC3-PIO0_12)") (class "Default")
      (node (ref "IC3") (pin "47") (pinfunction "PIO0_12_47") (pintype "tri_state"))
      (node (ref "IC5") (pin "8") (pinfunction "D5_8") (pintype "bidirectional"))
    )
    (net (code "44") (name "Net-(IC3-PIO0_13)") (class "Default")
      (node (ref "IC3") (pin "48") (pinfunction "PIO0_13_48") (pintype "tri_state"))
      (node (ref "IC5") (pin "16") (pinfunction "D6_16") (pintype "bidirectional"))
    )
    (net (code "45") (name "Net-(IC3-PIO0_14)") (class "Default")
      (node (ref "IC3") (pin "49") (pinfunction "PIO0_14_49") (pintype "tri_state"))
      (node (ref "IC5") (pin "10") (pinfunction "D7_10") (pintype "bidirectional"))
    )
    (net (code "46") (name "Net-(IC3-PIO0_15)") (class "Default")
      (node (ref "CON1") (pin "6") (pinfunction "6_6") (pintype "passive"))
      (node (ref "IC3") (pin "50") (pinfunction "PIO0_15_50") (pintype "tri_state"))
    )
    (net (code "47") (name "Net-(IC3-PIO0_16)") (class "Default")
      (node (ref "CON1") (pin "4") (pinfunction "4_4") (pintype "passive"))
      (node (ref "IC3") (pin "52") (pinfunction "PIO0_16_52") (pintype "tri_state"))
    )
    (net (code "48") (name "Net-(IC3-PIO0_17)") (class "Default")
      (node (ref "CON1") (pin "2") (pinfunction "2_2") (pintype "passive"))
      (node (ref "IC3") (pin "53") (pinfunction "PIO0_17_53") (pintype "tri_state"))
    )
    (net (code "49") (name "Net-(IC3-PIO0_18)") (class "Default")
      (node (ref "IC3") (pin "58") (pinfunction "PIO0_18_58") (pintype "tri_state"))
      (node (ref "IC5") (pin "5") (pinfunction "RS0_5") (pintype "input"))
    )
    (net (code "50") (name "Net-(IC3-PIO0_19)") (class "Default")
      (node (ref "IC3") (pin "59") (pinfunction "PIO0_19_59") (pintype "tri_state"))
      (node (ref "IC5") (pin "6") (pinfunction "RS1_6") (pintype "input"))
    )
    (net (code "51") (name "Net-(IC3-PIO0_20)") (class "Default")
      (node (ref "IC3") (pin "60") (pinfunction "PIO0_20_60") (pintype "tri_state"))
      (node (ref "IC5") (pin "3") (pinfunction "RNOTW_3") (pintype "input"))
    )
    (net (code "52") (name "Net-(IC3-PIO0_21)") (class "Default")
      (node (ref "IC3") (pin "61") (pinfunction "PIO0_21_61") (pintype "tri_state"))
      (node (ref "TP4") (pin "P$1") (pinfunction "P$1_P$1") (pintype "passive"))
    )
    (net (code "53") (name "Net-(IC3-PIO0_22)") (class "Default")
      (node (ref "IC3") (pin "63") (pinfunction "PIO0_22_63") (pintype "tri_state"))
      (node (ref "IC5") (pin "21") (pinfunction "NOTCS_21") (pintype "input"))
    )
    (net (code "54") (name "Net-(IC3-PIO0_23)") (class "Default")
      (node (ref "IC3") (pin "1") (pinfunction "PIO0_23_1") (pintype "tri_state"))
      (node (ref "IC5") (pin "4") (pinfunction "OUTPUTINT_4") (pintype "output"))
    )
    (net (code "55") (name "Net-(IC3-PIO0_24)") (class "Default")
      (node (ref "IC3") (pin "2") (pinfunction "PIO0_24_2") (pintype "tri_state"))
      (node (ref "IC5") (pin "22") (pinfunction "INPUTINT_22") (pintype "output"))
    )
    (net (code "56") (name "Net-(IC3-PIO0_25)") (class "Default")
      (node (ref "IC3") (pin "3") (pinfunction "PIO0_25_3") (pintype "tri_state"))
      (node (ref "IC5") (pin "11") (pinfunction "RESET_11") (pintype "input"))
      (node (ref "R21") (pin "1") (pinfunction "1_1") (pintype "passive"))
    )
    (net (code "57") (name "Net-(IC3-PIO1_6)") (class "Default")
      (node (ref "IC3") (pin "26") (pinfunction "PIO1_6_26") (pintype "tri_state"))
      (node (ref "R5") (pin "1") (pinfunction "1_1") (pintype "passive"))
      (node (ref "R6") (pin "2") (pinfunction "2_2") (pintype "passive"))
    )
    (net (code "58") (name "Net-(IC3-RESET)") (class "Default")
      (node (ref "CON1") (pin "10") (pinfunction "10_10") (pintype "passive"))
      (node (ref "IC3") (pin "64") (pinfunction "RESET_64") (pintype "tri_state"))
      (node (ref "R4") (pin "1") (pinfunction "1_1") (pintype "passive"))
    )
    (net (code "59") (name "Net-(IC3-USB_DM)") (class "Default")
      (node (ref "IC3") (pin "6") (pinfunction "USB_DM_6") (pintype "tri_state"))
      (node (ref "R7") (pin "2") (pinfunction "2_2") (pintype "passive"))
    )
    (net (code "60") (name "Net-(IC3-USB_DP)") (class "Default")
      (node (ref "IC3") (pin "5") (pinfunction "USB_DP_5") (pintype "tri_state"))
      (node (ref "R8") (pin "2") (pinfunction "2_2") (pintype "passive"))
    )
    (net (code "61") (name "Net-(IC5-CAPMINUS)") (class "Default")
      (node (ref "C9") (pin "2") (pinfunction "2_2") (pintype "passive"))
      (node (ref "IC5") (pin "23") (pinfunction "CAPMINUS_23") (pintype "passive"))
    )
    (net (code "62") (name "Net-(IC5-CLOCKIN)") (class "Default")
      (node (ref "IC5") (pin "13") (pinfunction "CLOCKIN_13") (pintype "input"))
      (node (ref "QG1") (pin "3") (pinfunction "FO_3") (pintype "output"))
    )
    (net (code "63") (name "Net-(IC5-LINKOUT)") (class "Default")
      (node (ref "IC5") (pin "1") (pinfunction "LINKOUT_1") (pintype "output"))
      (node (ref "R24") (pin "2") (pinfunction "2_2") (pintype "passive"))
    )
    (net (code "64") (name "Net-(IC6-IN--Pad14)") (class "Default")
      (node (ref "IC6") (pin "14") (pinfunction "IN-_14") (pintype "passive"))
      (node (ref "IC6") (pin "15") (pinfunction "IN-_15") (pintype "passive"))
      (node (ref "IC6") (pin "16") (pinfunction "IN-_16") (pintype "passive"))
      (node (ref "SCREW1") (pin "P$1") (pinfunction "P$1_P$1") (pintype "bidirectional"))
      (node (ref "SCREW3") (pin "P$1") (pinfunction "P$1_P$1") (pintype "bidirectional"))
      (node (ref "SV1") (pin "22") (pinfunction "22_22") (pintype "passive"))
      (node (ref "SV1") (pin "24") (pinfunction "24_24") (pintype "passive"))
      (node (ref "SV1") (pin "26") (pinfunction "26_26") (pintype "passive"))
      (node (ref "SV1") (pin "28") (pinfunction "28_28") (pintype "passive"))
      (node (ref "SV1") (pin "30") (pinfunction "30_30") (pintype "passive"))
      (node (ref "SV1") (pin "31") (pinfunction "31_31") (pintype "passive"))
      (node (ref "SV1") (pin "32") (pinfunction "32_32") (pintype "passive"))
      (node (ref "SV1") (pin "33") (pinfunction "33_33") (pintype "passive"))
      (node (ref "SV1") (pin "34") (pinfunction "34_34") (pintype "passive"))
      (node (ref "SV1") (pin "35") (pinfunction "35_35") (pintype "passive"))
      (node (ref "SV1") (pin "36") (pinfunction "36_36") (pintype "passive"))
      (node (ref "SV1") (pin "37") (pinfunction "37_37") (pintype "passive"))
      (node (ref "SV1") (pin "38") (pinfunction "38_38") (pintype "passive"))
      (node (ref "SV1") (pin "39") (pinfunction "39_39") (pintype "passive"))
      (node (ref "SV1") (pin "40") (pinfunction "40_40") (pintype "passive"))
    )
    (net (code "65") (name "Net-(IC7A-O)") (class "Default")
      (node (ref "IC7") (pin "3") (pinfunction "O_3") (pintype "output"))
      (node (ref "R17") (pin "1") (pinfunction "1_1") (pintype "passive"))
    )
    (net (code "66") (name "Net-(IC7B-O)") (class "Default")
      (node (ref "IC7") (pin "6") (pinfunction "O_6") (pintype "output"))
      (node (ref "R18") (pin "1") (pinfunction "1_1") (pintype "passive"))
    )
    (net (code "67") (name "Net-(IC7C-I0)") (class "Default")
      (node (ref "IC7") (pin "9") (pinfunction "I0_9") (pintype "input"))
      (node (ref "R16") (pin "1") (pinfunction "1_1") (pintype "passive"))
    )
    (net (code "68") (name "Net-(IC8-+VOUT)") (class "Default")
      (node (ref "IC8") (pin "6") (pinfunction "+VOUT_6") (pintype "passive"))
      (node (ref "J2") (pin "2") (pinfunction "S_2") (pintype "passive"))
      (node (ref "J3") (pin "2") (pinfunction "S_2") (pintype "passive"))
    )
    (net (code "69") (name "Net-(IC9-IO1)") (class "Default")
      (node (ref "IC9") (pin "2") (pinfunction "IO1_2") (pintype "passive"))
      (node (ref "J4") (pin "4") (pinfunction "4_4") (pintype "passive"))
      (node (ref "R17") (pin "2") (pinfunction "2_2") (pintype "passive"))
    )
    (net (code "70") (name "Net-(IC9-IO2)") (class "Default")
      (node (ref "IC9") (pin "3") (pinfunction "IO2_3") (pintype "passive"))
      (node (ref "J4") (pin "3") (pinfunction "3_3") (pintype "passive"))
      (node (ref "R16") (pin "2") (pinfunction "2_2") (pintype "passive"))
      (node (ref "R19") (pin "1") (pinfunction "1_1") (pintype "passive"))
    )
    (net (code "71") (name "Net-(IC10-DO+)") (class "Default")
      (node (ref "IC10") (pin "6") (pinfunction "DO+_6") (pintype "output"))
      (node (ref "J4") (pin "7") (pinfunction "7_7") (pintype "passive"))
    )
    (net (code "72") (name "Net-(IC10-DO-)") (class "Default")
      (node (ref "IC10") (pin "5") (pinfunction "DO-_5") (pintype "output"))
      (node (ref "J4") (pin "8") (pinfunction "8_8") (pintype "passive"))
    )
    (net (code "73") (name "Net-(IC10-RI+)") (class "Default")
      (node (ref "IC10") (pin "8") (pinfunction "RI+_8") (pintype "input"))
      (node (ref "J4") (pin "1") (pinfunction "1_1") (pintype "passive"))
      (node (ref "R20") (pin "1") (pinfunction "1_1") (pintype "passive"))
      (node (ref "R22") (pin "1") (pinfunction "1_1") (pintype "passive"))
    )
    (net (code "74") (name "Net-(IC10-RI-)") (class "Default")
      (node (ref "IC10") (pin "7") (pinfunction "RI-_7") (pintype "input"))
      (node (ref "J4") (pin "2") (pinfunction "2_2") (pintype "passive"))
      (node (ref "R20") (pin "2") (pinfunction "2_2") (pintype "passive"))
      (node (ref "R23") (pin "1") (pinfunction "1_1") (pintype "passive"))
    )
    (net (code "75") (name "Net-(IC10-RO)") (class "Default")
      (node (ref "IC10") (pin "2") (pinfunction "RO_2") (pintype "output"))
      (node (ref "IC7") (pin "12") (pinfunction "I0_12") (pintype "input"))
    )
    (net (code "76") (name "Net-(IC11-IO1)") (class "Default")
      (node (ref "IC11") (pin "2") (pinfunction "IO1_2") (pintype "passive"))
      (node (ref "J4") (pin "5") (pinfunction "5_5") (pintype "passive"))
      (node (ref "R18") (pin "2") (pinfunction "2_2") (pintype "passive"))
    )
    (net (code "77") (name "Net-(IC12-SCL)") (class "Default")
      (node (ref "IC12") (pin "14") (pinfunction "SCL_14") (pintype "input"))
      (node (ref "IC13") (pin "14") (pinfunction "SCL_14") (pintype "input"))
      (node (ref "J5") (pin "4") (pinfunction "S_4") (pintype "passive"))
    )
    (net (code "78") (name "Net-(IC12-SDA)") (class "Default")
      (node (ref "IC12") (pin "15") (pinfunction "SDA_15") (pintype "bidirectional"))
      (node (ref "IC13") (pin "15") (pinfunction "SDA_15") (pintype "bidirectional"))
      (node (ref "J5") (pin "3") (pinfunction "S_3") (pintype "passive"))
    )
    (net (code "79") (name "Net-(J5B-S)") (class "Default")
      (node (ref "J5") (pin "2") (pinfunction "S_2") (pintype "passive"))
      (node (ref "J6") (pin "2") (pinfunction "S_2") (pintype "passive"))
    )
    (net (code "80") (name "Net-(LED1-PadC)") (class "Default")
      (node (ref "LED1") (pin "C") (pinfunction "C_C") (pintype "passive"))
      (node (ref "R12") (pin "2") (pinfunction "2_2") (pintype "passive"))
    )
    (net (code "81") (name "Net-(LED2-PadC)") (class "Default")
      (node (ref "LED2") (pin "C") (pinfunction "C_C") (pintype "passive"))
      (node (ref "R13") (pin "2") (pinfunction "2_2") (pintype "passive"))
    )
    (net (code "82") (name "Net-(R9-Pad2)") (class "Default")
      (node (ref "R9") (pin "2") (pinfunction "2_2") (pintype "passive"))
      (node (ref "SP1") (pin "2") (pinfunction "2_2") (pintype "passive"))
    )
    (net (code "83") (name "OUT0") (class "Default")
      (node (ref "IC5") (pin "2") (pinfunction "LINKIN_2") (pintype "input"))
      (node (ref "SV1") (pin "27") (pinfunction "27_27") (pintype "passive"))
    )
    (net (code "84") (name "OUT1") (class "Default")
      (node (ref "IC10") (pin "3") (pinfunction "DI_3") (pintype "input"))
      (node (ref "SV1") (pin "23") (pinfunction "23_23") (pintype "passive"))
    )
    (net (code "85") (name "PON") (class "Default")
      (node (ref "IC3") (pin "37") (pinfunction "PIO0_3_37") (pintype "tri_state"))
      (node (ref "IC4") (pin "2") (pinfunction "IN_2") (pintype "input"))
      (node (ref "IC7") (pin "13") (pinfunction "I1_13") (pintype "input"))
      (node (ref "R10") (pin "2") (pinfunction "2_2") (pintype "passive"))
    )
    (net (code "86") (name "RESET") (class "Default")
      (node (ref "IC3") (pin "36") (pinfunction "PIO0_2_36") (pintype "tri_state"))
      (node (ref "IC7") (pin "1") (pinfunction "I0_1") (pintype "input"))
      (node (ref "IC7") (pin "2") (pinfunction "I1_2") (pintype "input"))
      (node (ref "SV1") (pin "17") (pinfunction "17_17") (pintype "passive"))
    )
    (net (code "87") (name "SCL") (class "Default")
      (node (ref "IC3") (pin "18") (pinfunction "PIO1_4_18") (pintype "tri_state"))
      (node (ref "IC6") (pin "9") (pinfunction "SCL_9") (pintype "bidirectional"))
      (node (ref "J1") (pin "4") (pinfunction "S_4") (pintype "passive"))
      (node (ref "R1") (pin "1") (pinfunction "1_1") (pintype "passive"))
    )
    (net (code "88") (name "SDA") (class "Default")
      (node (ref "IC3") (pin "19") (pinfunction "PIO1_5_19") (pintype "tri_state"))
      (node (ref "IC6") (pin "8") (pinfunction "SDA_8") (pintype "bidirectional"))
      (node (ref "J1") (pin "3") (pinfunction "S_3") (pintype "passive"))
      (node (ref "R2") (pin "1") (pinfunction "1_1") (pintype "passive"))
    )
    (net (code "89") (name "SPEAKER") (class "Default")
      (node (ref "IC3") (pin "51") (pinfunction "PIO1_12_51") (pintype "tri_state"))
      (node (ref "R9") (pin "1") (pinfunction "1_1") (pintype "passive"))
    )
    (net (code "90") (name "TEST") (class "Default")
      (node (ref "IC3") (pin "40") (pinfunction "PIO0_6_40") (pintype "tri_state"))
      (node (ref "SV1") (pin "11") (pinfunction "11_11") (pintype "passive"))
    )
    (net (code "91") (name "VCC") (class "Default")
      (node (ref "C11") (pin "1") (pinfunction "1_1") (pintype "passive"))
      (node (ref "C13") (pin "1") (pinfunction "1_1") (pintype "passive"))
      (node (ref "C14") (pin "1") (pinfunction "1_1") (pintype "passive"))
      (node (ref "C2") (pin "+") (pinfunction "+_+") (pintype "passive"))
      (node (ref "C3") (pin "1") (pinfunction "1_1") (pintype "passive"))
      (node (ref "CON2") (pin "2") (pinfunction "2_2") (pintype "passive"))
      (node (ref "IC10") (pin "1") (pinfunction "VCC_1") (pintype "power_in"))
      (node (ref "IC11") (pin "4") (pinfunction "VCC_4") (pintype "power_in"))
      (node (ref "IC2") (pin "3") (pinfunction "IN_3") (pintype "input"))
      (node (ref "IC4") (pin "6") (pinfunction "VBB_6") (pintype "passive"))
      (node (ref "IC6") (pin "10") (pinfunction "VS_10") (pintype "power_in"))
      (node (ref "IC6") (pin "12") (pinfunction "VBUS_12") (pintype "passive"))
      (node (ref "IC7") (pin "14") (pinfunction "VCC_14") (pintype "power_in"))
      (node (ref "IC9") (pin "4") (pinfunction "VCC_4") (pintype "power_in"))
      (node (ref "J1") (pin "5") (pinfunction "S_5") (pintype "passive"))
      (node (ref "LED1") (pin "A") (pinfunction "A_A") (pintype "passive"))
      (node (ref "R1") (pin "2") (pinfunction "2_2") (pintype "passive"))
      (node (ref "R14") (pin "2") (pinfunction "2_2") (pintype "passive"))
      (node (ref "R15") (pin "2") (pinfunction "2_2") (pintype "passive"))
      (node (ref "R19") (pin "2") (pinfunction "2_2") (pintype "passive"))
      (node (ref "R2") (pin "2") (pinfunction "2_2") (pintype "passive"))
      (node (ref "R23") (pin "2") (pinfunction "2_2") (pintype "passive"))
    )
    (net (code "92") (name "VCCINT") (class "Default")
      (node (ref "C10") (pin "1") (pinfunction "1_1") (pintype "passive"))
      (node (ref "C12") (pin "1") (pinfunction "1_1") (pintype "passive"))
      (node (ref "C9") (pin "1") (pinfunction "1_1") (pintype "passive"))
      (node (ref "IC4") (pin "5") (pinfunction "OUT_5") (pintype "output"))
      (node (ref "IC5") (pin "24") (pinfunction "VCC_24") (pintype "power_in"))
      (node (ref "IC6") (pin "1") (pinfunction "IN+_1") (pintype "passive"))
      (node (ref "IC6") (pin "2") (pinfunction "IN+_2") (pintype "passive"))
      (node (ref "IC6") (pin "3") (pinfunction "IN+_3") (pintype "passive"))
      (node (ref "IC8") (pin "2") (pinfunction "+VIN_2") (pintype "passive"))
      (node (ref "LED2") (pin "A") (pinfunction "A_A") (pintype "passive"))
      (node (ref "QG1") (pin "1") (pinfunction "OE_1") (pintype "input"))
      (node (ref "QG1") (pin "4") (pinfunction "VCC_4") (pintype "power_in"))
      (node (ref "R21") (pin "2") (pinfunction "2_2") (pintype "passive"))
    )
    (net (code "93") (name "VDD") (class "Default")
      (node (ref "C4") (pin "1") (pinfunction "1_1") (pintype "passive"))
      (node (ref "C5") (pin "1") (pinfunction "1_1") (pintype "passive"))
      (node (ref "C6") (pin "1") (pinfunction "1_1") (pintype "passive"))
      (node (ref "C7") (pin "+") (pinfunction "+_+") (pintype "passive"))
      (node (ref "C8") (pin "1") (pinfunction "1_1") (pintype "passive"))
      (node (ref "CON1") (pin "1") (pinfunction "1_1") (pintype "passive"))
      (node (ref "IC2") (pin "2") (pinfunction "OUT_2") (pintype "passive"))
      (node (ref "IC3") (pin "22") (pinfunction "VREFP_22") (pintype "tri_state"))
      (node (ref "IC3") (pin "23") (pinfunction "VCCA_23") (pintype "power_in"))
      (node (ref "IC3") (pin "24") (pinfunction "VCC_24") (pintype "power_in"))
      (node (ref "IC3") (pin "34") (pinfunction "VCC_34") (pintype "power_in"))
      (node (ref "IC3") (pin "56") (pinfunction "VCC_56") (pintype "power_in"))
      (node (ref "IC3") (pin "8") (pinfunction "VCC_8") (pintype "power_in"))
      (node (ref "R11") (pin "2") (pinfunction "2_2") (pintype "passive"))
      (node (ref "R3") (pin "2") (pinfunction "2_2") (pintype "passive"))
      (node (ref "R4") (pin "2") (pinfunction "2_2") (pintype "passive"))
    )
    (net (code "94") (name "unconnected-(CON1-Pad7)") (class "Default")
      (node (ref "CON1") (pin "7") (pinfunction "7_7") (pintype "passive"))
    )
    (net (code "95") (name "unconnected-(CON1-Pad8)") (class "Default")
      (node (ref "CON1") (pin "8") (pinfunction "8_8") (pintype "passive"))
    )
    (net (code "96") (name "unconnected-(DIS1-CLK-Pad12)") (class "Default")
      (node (ref "DIS1") (pin "12") (pinfunction "CLK_12") (pintype "input"))
    )
    (net (code "97") (name "unconnected-(DIS1-SUB1-Pad7)") (class "Default")
      (node (ref "DIS1") (pin "7") (pinfunction "SUB1_7") (pintype "passive"))
    )
    (net (code "98") (name "unconnected-(DIS1-SUB2-Pad8)") (class "Default")
      (node (ref "DIS1") (pin "8") (pinfunction "SUB2_8") (pintype "passive"))
    )
    (net (code "99") (name "unconnected-(DIS1-SUB3-Pad9)") (class "Default")
      (node (ref "DIS1") (pin "9") (pinfunction "SUB3_9") (pintype "passive"))
    )
    (net (code "100") (name "unconnected-(IC3-PIO0_26-Pad4)") (class "Default")
      (node (ref "IC3") (pin "4") (pinfunction "PIO0_26_4") (pintype "tri_state"))
    )
    (net (code "101") (name "unconnected-(IC3-PIO0_29-Pad11)") (class "Default")
      (node (ref "IC3") (pin "11") (pinfunction "PIO0_29_11") (pintype "tri_state"))
    )
    (net (code "102") (name "unconnected-(IC3-PIO0_30-Pad12)") (class "Default")
      (node (ref "IC3") (pin "12") (pinfunction "PIO0_30_12") (pintype "tri_state"))
    )
    (net (code "103") (name "unconnected-(IC3-PIO1_2-Pad16)") (class "Default")
      (node (ref "IC3") (pin "16") (pinfunction "PIO1_2_16") (pintype "tri_state"))
    )
    (net (code "104") (name "unconnected-(IC3-PIO1_7-Pad27)") (class "Default")
      (node (ref "IC3") (pin "27") (pinfunction "PIO1_7_27") (pintype "tri_state"))
    )
    (net (code "105") (name "unconnected-(IC3-PIO1_8-Pad28)") (class "Default")
      (node (ref "IC3") (pin "28") (pinfunction "PIO1_8_28") (pintype "tri_state"))
    )
    (net (code "106") (name "unconnected-(IC3-PIO1_11-Pad42)") (class "Default")
      (node (ref "IC3") (pin "42") (pinfunction "PIO1_11_42") (pintype "tri_state"))
    )
    (net (code "107") (name "unconnected-(IC3-PIO1_13-Pad54)") (class "Default")
      (node (ref "IC3") (pin "54") (pinfunction "PIO1_13_54") (pintype "tri_state"))
    )
    (net (code "108") (name "unconnected-(IC3-PIO1_14-Pad57)") (class "Default")
      (node (ref "IC3") (pin "57") (pinfunction "PIO1_14_57") (pintype "tri_state"))
    )
    (net (code "109") (name "unconnected-(IC3-PIO1_15-Pad62)") (class "Default")
      (node (ref "IC3") (pin "62") (pinfunction "PIO1_15_62") (pintype "tri_state"))
    )
    (net (code "110") (name "unconnected-(IC3-PIO1_16-Pad7)") (class "Default")
      (node (ref "IC3") (pin "7") (pinfunction "PIO1_16_7") (pintype "tri_state"))
    )
    (net (code "111") (name "unconnected-(IC3-PIO1_17-Pad10)") (class "Default")
      (node (ref "IC3") (pin "10") (pinfunction "PIO1_17_10") (pintype "tri_state"))
    )
    (net (code "112") (name "unconnected-(IC3-RTCXOUT-Pad35)") (class "Default")
      (node (ref "IC3") (pin "35") (pinfunction "RTCXOUT_35") (pintype "tri_state"))
    )
    (net (code "113") (name "unconnected-(IC6-ALERT-Pad7)") (class "Default")
      (node (ref "IC6") (pin "7") (pinfunction "ALERT_7") (pintype "output"))
    )
    (net (code "114") (name "unconnected-(IC11-IO2-Pad3)") (class "Default")
      (node (ref "IC11") (pin "3") (pinfunction "IO2_3") (pintype "passive"))
    )
    (net (code "115") (name "unconnected-(IC12-~{INT}-Pad13)") (class "Default")
      (node (ref "IC12") (pin "13") (pinfunction "~{INT}_13") (pintype "output"))
    )
    (net (code "116") (name "unconnected-(IC13-~{INT}-Pad13)") (class "Default")
      (node (ref "IC13") (pin "13") (pinfunction "~{INT}_13") (pintype "output"))
    )
    (net (code "117") (name "unconnected-(X1-Pad4)") (class "Default")
      (node (ref "X1") (pin "4") (pinfunction "4_4") (pintype "input"))
    )
  )
)
